# xy-pad.net
KiCad netlist of a schematic drawn in EAGLE
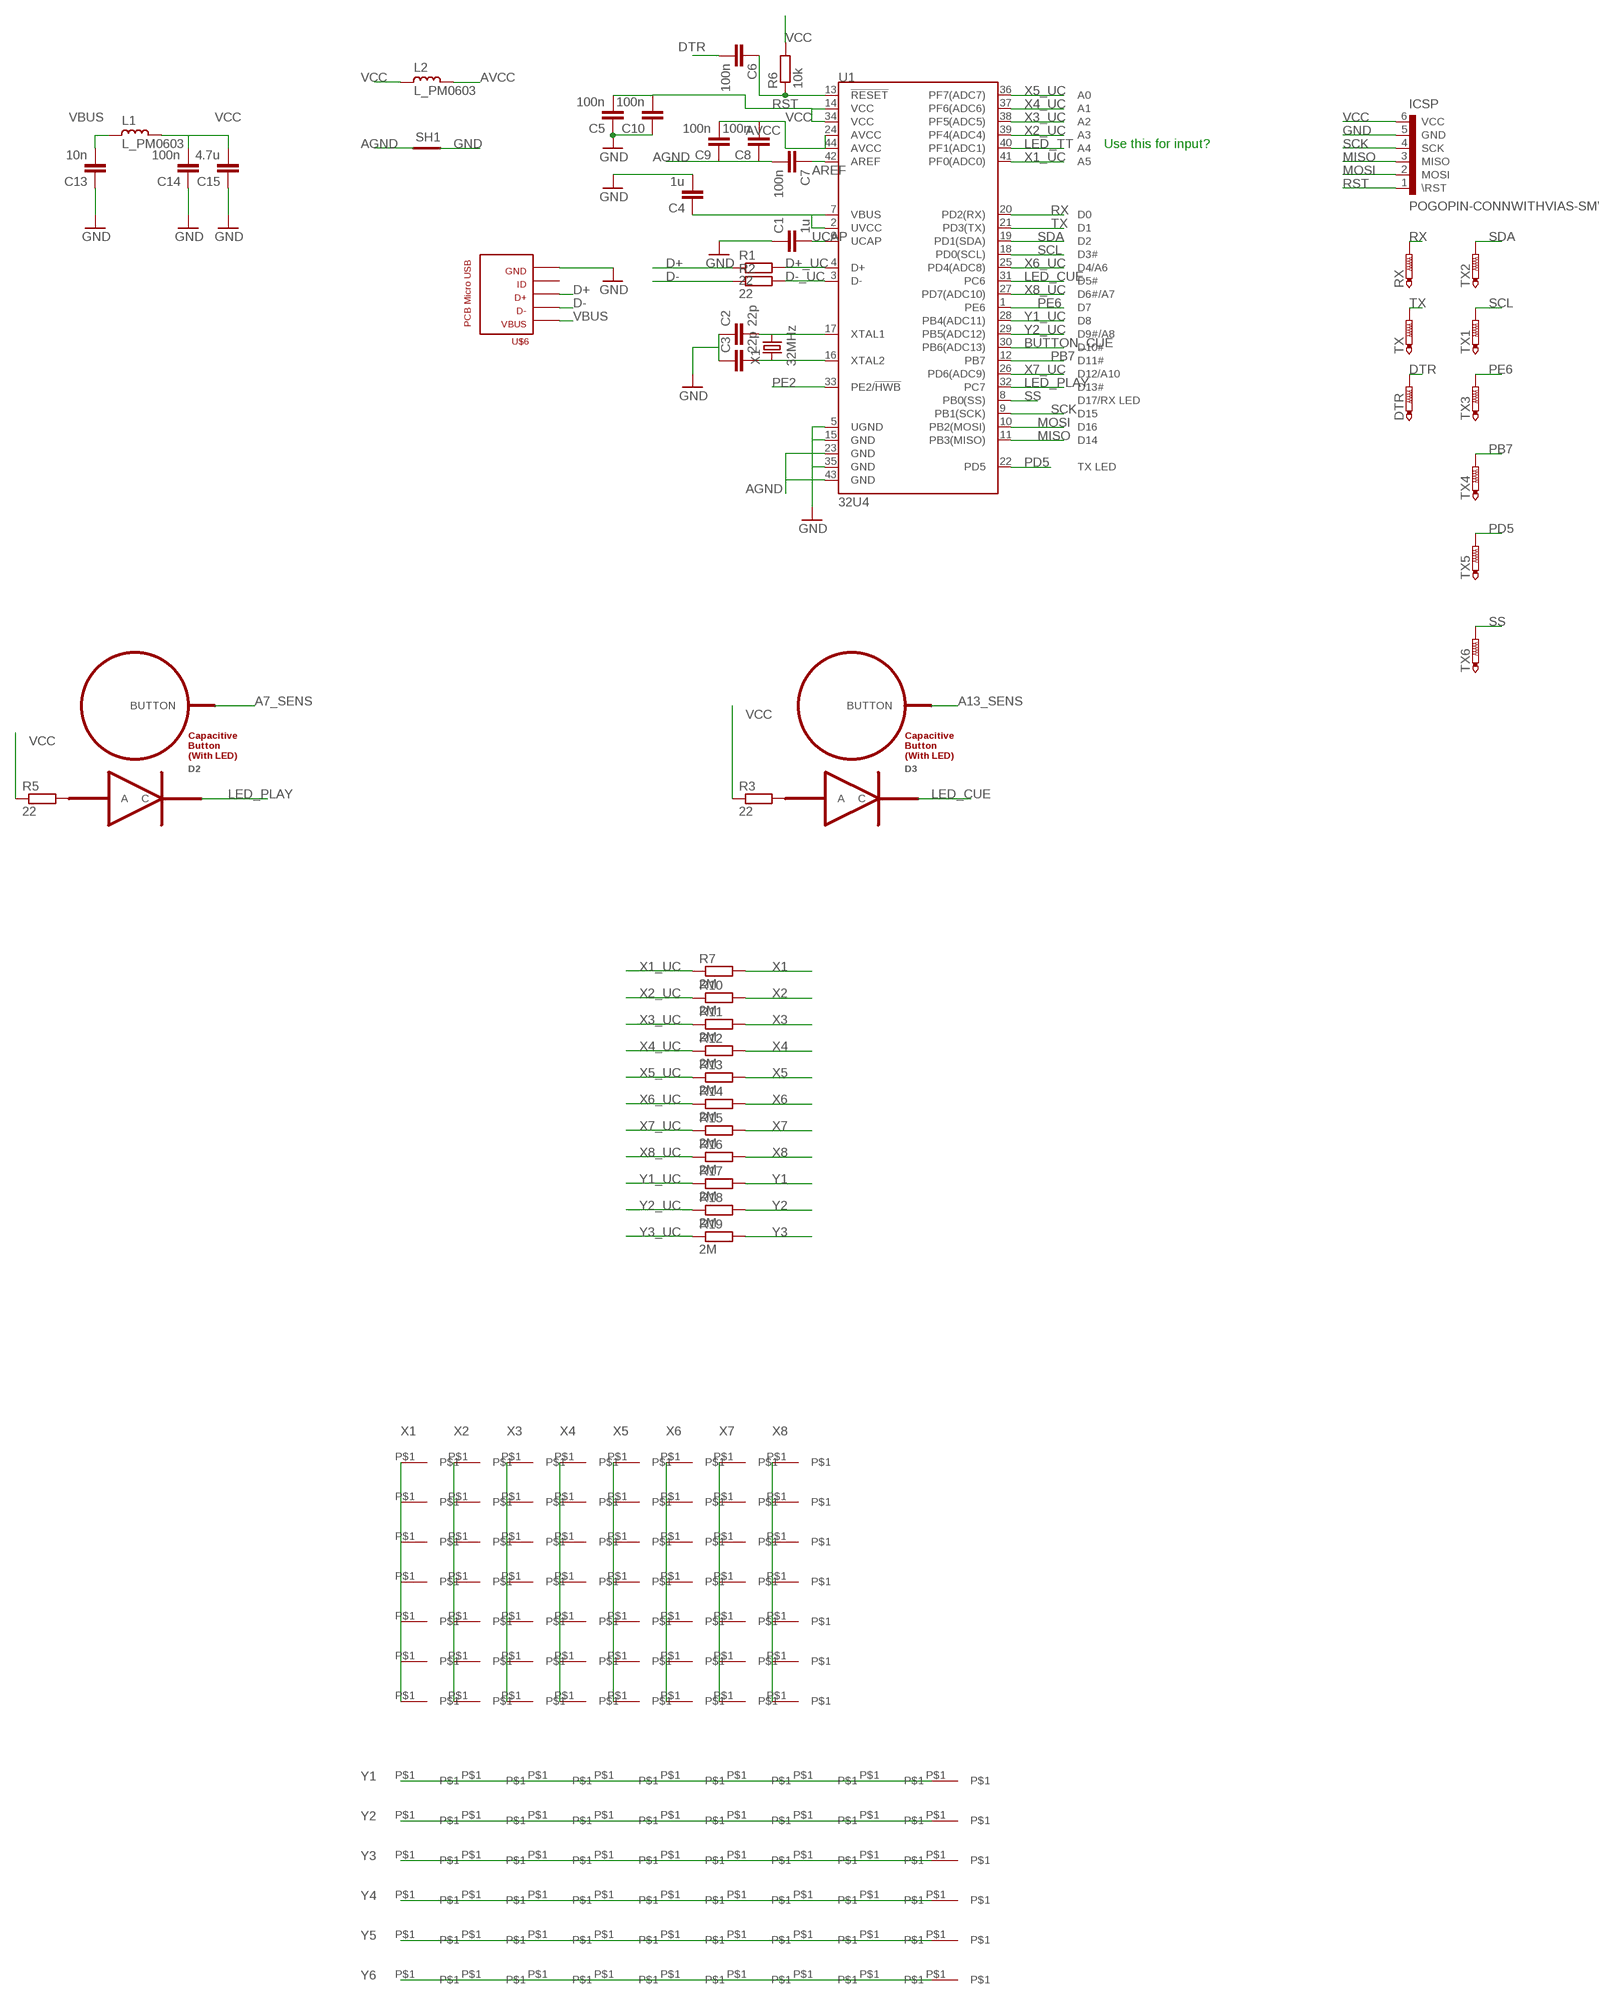
[diagram p0: schematic, sheet 1]

(export (version "E")
  (design (tool "Eeschema 10.0.6"))
  (components
    (comp (ref "C1")
      (value "1u")
      (footprint "eagle-import:C0402")
      (libsource (lib "eagle-import") (part "C-EUC0402"))
    )
    (comp (ref "C2")
      (value "22p")
      (footprint "eagle-import:C0402")
      (libsource (lib "eagle-import") (part "C-EUC0402"))
    )
    (comp (ref "C3")
      (value "22p")
      (footprint "eagle-import:C0402")
      (libsource (lib "eagle-import") (part "C-EUC0402"))
    )
    (comp (ref "C4")
      (value "1u")
      (footprint "eagle-import:C0402")
      (libsource (lib "eagle-import") (part "C-EUC0402"))
    )
    (comp (ref "C5")
      (value "100n")
      (footprint "eagle-import:C0402")
      (libsource (lib "eagle-import") (part "C-EUC0402"))
    )
    (comp (ref "C6")
      (value "100n")
      (footprint "eagle-import:C0402")
      (libsource (lib "eagle-import") (part "C-EUC0402"))
    )
    (comp (ref "C7")
      (value "100n")
      (footprint "eagle-import:C0402")
      (libsource (lib "eagle-import") (part "C-EUC0402"))
    )
    (comp (ref "C8")
      (value "100n")
      (footprint "eagle-import:C0402")
      (libsource (lib "eagle-import") (part "C-EUC0402"))
    )
    (comp (ref "C9")
      (value "100n")
      (footprint "eagle-import:C0402")
      (libsource (lib "eagle-import") (part "C-EUC0402"))
    )
    (comp (ref "C10")
      (value "100n")
      (footprint "eagle-import:C0402")
      (libsource (lib "eagle-import") (part "C-EUC0402"))
    )
    (comp (ref "C13")
      (value "10n")
      (footprint "eagle-import:C0402")
      (libsource (lib "eagle-import") (part "C-EUC0402"))
    )
    (comp (ref "C14")
      (value "100n")
      (footprint "eagle-import:C0402")
      (libsource (lib "eagle-import") (part "C-EUC0402"))
    )
    (comp (ref "C15")
      (value "4.7u")
      (footprint "eagle-import:C0402")
      (libsource (lib "eagle-import") (part "C-EUC0402"))
    )
    (comp (ref "D2")
      (value "LED_BUTTON")
      (footprint "eagle-import:LED_BUTTON")
      (libsource (lib "eagle-import") (part "LED_BUTTON"))
    )
    (comp (ref "D3")
      (value "LED_BUTTON")
      (footprint "eagle-import:LED_BUTTON")
      (libsource (lib "eagle-import") (part "LED_BUTTON"))
    )
    (comp (ref "DTR")
      (value "PTR1TP06R")
      (footprint "eagle-import:TP06R")
      (libsource (lib "eagle-import") (part "PTR1TP06R"))
    )
    (comp (ref "ICSP")
      (value "POGOPIN-CONNWITHVIAS-SMV")
      (footprint "eagle-import:POGOPROG-CONN-OH-SMALLERVIAS")
      (libsource (lib "eagle-import") (part "POGOPIN-CONNWITHVIAS-SMV"))
    )
    (comp (ref "L1")
      (value "L_PM0603")
      (footprint "eagle-import:PM0603")
      (libsource (lib "eagle-import") (part "L_PM0603"))
    )
    (comp (ref "L2")
      (value "L_PM0603")
      (footprint "eagle-import:PM0603")
      (libsource (lib "eagle-import") (part "L_PM0603"))
    )
    (comp (ref "R1")
      (value "22")
      (footprint "eagle-import:R0402")
      (libsource (lib "eagle-import") (part "R-EU_R0402"))
    )
    (comp (ref "R2")
      (value "22")
      (footprint "eagle-import:R0402")
      (libsource (lib "eagle-import") (part "R-EU_R0402"))
    )
    (comp (ref "R3")
      (value "22")
      (footprint "eagle-import:R0402")
      (libsource (lib "eagle-import") (part "R-EU_R0402"))
    )
    (comp (ref "R5")
      (value "22")
      (footprint "eagle-import:R0402")
      (libsource (lib "eagle-import") (part "R-EU_R0402"))
    )
    (comp (ref "R6")
      (value "10k")
      (footprint "eagle-import:R0402")
      (libsource (lib "eagle-import") (part "R-EU_R0402"))
    )
    (comp (ref "R7")
      (value "2M")
      (footprint "eagle-import:R0402")
      (libsource (lib "eagle-import") (part "R-EU_R0402"))
    )
    (comp (ref "R10")
      (value "2M")
      (footprint "eagle-import:R0402")
      (libsource (lib "eagle-import") (part "R-EU_R0402"))
    )
    (comp (ref "R11")
      (value "2M")
      (footprint "eagle-import:R0402")
      (libsource (lib "eagle-import") (part "R-EU_R0402"))
    )
    (comp (ref "R12")
      (value "2M")
      (footprint "eagle-import:R0402")
      (libsource (lib "eagle-import") (part "R-EU_R0402"))
    )
    (comp (ref "R13")
      (value "2M")
      (footprint "eagle-import:R0402")
      (libsource (lib "eagle-import") (part "R-EU_R0402"))
    )
    (comp (ref "R14")
      (value "2M")
      (footprint "eagle-import:R0402")
      (libsource (lib "eagle-import") (part "R-EU_R0402"))
    )
    (comp (ref "R15")
      (value "2M")
      (footprint "eagle-import:R0402")
      (libsource (lib "eagle-import") (part "R-EU_R0402"))
    )
    (comp (ref "R16")
      (value "2M")
      (footprint "eagle-import:R0402")
      (libsource (lib "eagle-import") (part "R-EU_R0402"))
    )
    (comp (ref "R17")
      (value "2M")
      (footprint "eagle-import:R0402")
      (libsource (lib "eagle-import") (part "R-EU_R0402"))
    )
    (comp (ref "R18")
      (value "2M")
      (footprint "eagle-import:R0402")
      (libsource (lib "eagle-import") (part "R-EU_R0402"))
    )
    (comp (ref "R19")
      (value "2M")
      (footprint "eagle-import:R0402")
      (libsource (lib "eagle-import") (part "R-EU_R0402"))
    )
    (comp (ref "RX")
      (value "PTR1TP06R")
      (footprint "eagle-import:TP06R")
      (libsource (lib "eagle-import") (part "PTR1TP06R"))
    )
    (comp (ref "SH1")
      (value "SHORT")
      (footprint "eagle-import:SHORT_TOP-6")
      (libsource (lib "eagle-import") (part "SHORT"))
    )
    (comp (ref "TX")
      (value "PTR1TP06R")
      (footprint "eagle-import:TP06R")
      (libsource (lib "eagle-import") (part "PTR1TP06R"))
    )
    (comp (ref "TX1")
      (value "PTR1TP06R")
      (footprint "eagle-import:TP06R")
      (libsource (lib "eagle-import") (part "PTR1TP06R"))
    )
    (comp (ref "TX2")
      (value "PTR1TP06R")
      (footprint "eagle-import:TP06R")
      (libsource (lib "eagle-import") (part "PTR1TP06R"))
    )
    (comp (ref "TX3")
      (value "PTR1TP06R")
      (footprint "eagle-import:TP06R")
      (libsource (lib "eagle-import") (part "PTR1TP06R"))
    )
    (comp (ref "TX4")
      (value "PTR1TP06R")
      (footprint "eagle-import:TP06R")
      (libsource (lib "eagle-import") (part "PTR1TP06R"))
    )
    (comp (ref "TX5")
      (value "PTR1TP06R")
      (footprint "eagle-import:TP06R")
      (libsource (lib "eagle-import") (part "PTR1TP06R"))
    )
    (comp (ref "TX6")
      (value "PTR1TP06R")
      (footprint "eagle-import:TP06R")
      (libsource (lib "eagle-import") (part "PTR1TP06R"))
    )
    (comp (ref "U$1")
      (value "XY_PAD")
      (footprint "eagle-import:DIAMOND_PAD")
      (libsource (lib "eagle-import") (part "XY_PAD"))
    )
    (comp (ref "U$2")
      (value "XY_PADTRIANGLE")
      (footprint "eagle-import:TRIANGLE_PAD")
      (libsource (lib "eagle-import") (part "XY_PADTRIANGLE"))
    )
    (comp (ref "U$3")
      (value "XY_PADTRIANGLE")
      (footprint "eagle-import:TRIANGLE_PAD")
      (libsource (lib "eagle-import") (part "XY_PADTRIANGLE"))
    )
    (comp (ref "U$4")
      (value "XY_PADTRIANGLE")
      (footprint "eagle-import:TRIANGLE_PAD")
      (libsource (lib "eagle-import") (part "XY_PADTRIANGLE"))
    )
    (comp (ref "U$5")
      (value "XY_PADTRIANGLE")
      (footprint "eagle-import:TRIANGLE_PAD")
      (libsource (lib "eagle-import") (part "XY_PADTRIANGLE"))
    )
    (comp (ref "U$6")
      (value "PCB_MICRO_USB_BSS_2")
      (footprint "eagle-import:USB_TYPE_B_SS_2")
      (libsource (lib "eagle-import") (part "PCB_MICRO_USB_BSS_2"))
    )
    (comp (ref "U$7")
      (value "XY_PADTRIANGLE")
      (footprint "eagle-import:TRIANGLE_PAD")
      (libsource (lib "eagle-import") (part "XY_PADTRIANGLE"))
    )
    (comp (ref "U$8")
      (value "XY_PADTRIANGLE")
      (footprint "eagle-import:TRIANGLE_PAD")
      (libsource (lib "eagle-import") (part "XY_PADTRIANGLE"))
    )
    (comp (ref "U$9")
      (value "XY_PADTRIANGLE")
      (footprint "eagle-import:TRIANGLE_PAD")
      (libsource (lib "eagle-import") (part "XY_PADTRIANGLE"))
    )
    (comp (ref "U$10")
      (value "XY_PADTRIANGLE")
      (footprint "eagle-import:TRIANGLE_PAD")
      (libsource (lib "eagle-import") (part "XY_PADTRIANGLE"))
    )
    (comp (ref "U$11")
      (value "XY_PAD")
      (footprint "eagle-import:DIAMOND_PAD")
      (libsource (lib "eagle-import") (part "XY_PAD"))
    )
    (comp (ref "U$12")
      (value "XY_PAD")
      (footprint "eagle-import:DIAMOND_PAD")
      (libsource (lib "eagle-import") (part "XY_PAD"))
    )
    (comp (ref "U$13")
      (value "XY_PAD")
      (footprint "eagle-import:DIAMOND_PAD")
      (libsource (lib "eagle-import") (part "XY_PAD"))
    )
    (comp (ref "U$14")
      (value "XY_PAD")
      (footprint "eagle-import:DIAMOND_PAD")
      (libsource (lib "eagle-import") (part "XY_PAD"))
    )
    (comp (ref "U$15")
      (value "XY_PAD")
      (footprint "eagle-import:DIAMOND_PAD")
      (libsource (lib "eagle-import") (part "XY_PAD"))
    )
    (comp (ref "U$16")
      (value "XY_PAD")
      (footprint "eagle-import:DIAMOND_PAD")
      (libsource (lib "eagle-import") (part "XY_PAD"))
    )
    (comp (ref "U$17")
      (value "XY_PAD")
      (footprint "eagle-import:DIAMOND_PAD")
      (libsource (lib "eagle-import") (part "XY_PAD"))
    )
    (comp (ref "U$18")
      (value "XY_PAD")
      (footprint "eagle-import:DIAMOND_PAD")
      (libsource (lib "eagle-import") (part "XY_PAD"))
    )
    (comp (ref "U$19")
      (value "XY_PAD")
      (footprint "eagle-import:DIAMOND_PAD")
      (libsource (lib "eagle-import") (part "XY_PAD"))
    )
    (comp (ref "U$20")
      (value "XY_PAD")
      (footprint "eagle-import:DIAMOND_PAD")
      (libsource (lib "eagle-import") (part "XY_PAD"))
    )
    (comp (ref "U$21")
      (value "XY_PAD")
      (footprint "eagle-import:DIAMOND_PAD")
      (libsource (lib "eagle-import") (part "XY_PAD"))
    )
    (comp (ref "U$22")
      (value "XY_PAD")
      (footprint "eagle-import:DIAMOND_PAD")
      (libsource (lib "eagle-import") (part "XY_PAD"))
    )
    (comp (ref "U$23")
      (value "XY_PAD")
      (footprint "eagle-import:DIAMOND_PAD")
      (libsource (lib "eagle-import") (part "XY_PAD"))
    )
    (comp (ref "U$24")
      (value "XY_PAD")
      (footprint "eagle-import:DIAMOND_PAD")
      (libsource (lib "eagle-import") (part "XY_PAD"))
    )
    (comp (ref "U$25")
      (value "XY_PAD")
      (footprint "eagle-import:DIAMOND_PAD")
      (libsource (lib "eagle-import") (part "XY_PAD"))
    )
    (comp (ref "U$26")
      (value "XY_PAD")
      (footprint "eagle-import:DIAMOND_PAD")
      (libsource (lib "eagle-import") (part "XY_PAD"))
    )
    (comp (ref "U$27")
      (value "XY_PAD")
      (footprint "eagle-import:DIAMOND_PAD")
      (libsource (lib "eagle-import") (part "XY_PAD"))
    )
    (comp (ref "U$28")
      (value "XY_PAD")
      (footprint "eagle-import:DIAMOND_PAD")
      (libsource (lib "eagle-import") (part "XY_PAD"))
    )
    (comp (ref "U$29")
      (value "XY_PAD")
      (footprint "eagle-import:DIAMOND_PAD")
      (libsource (lib "eagle-import") (part "XY_PAD"))
    )
    (comp (ref "U$30")
      (value "XY_PAD")
      (footprint "eagle-import:DIAMOND_PAD")
      (libsource (lib "eagle-import") (part "XY_PAD"))
    )
    (comp (ref "U$31")
      (value "XY_PAD")
      (footprint "eagle-import:DIAMOND_PAD")
      (libsource (lib "eagle-import") (part "XY_PAD"))
    )
    (comp (ref "U$32")
      (value "XY_PAD")
      (footprint "eagle-import:DIAMOND_PAD")
      (libsource (lib "eagle-import") (part "XY_PAD"))
    )
    (comp (ref "U$33")
      (value "XY_PAD")
      (footprint "eagle-import:DIAMOND_PAD")
      (libsource (lib "eagle-import") (part "XY_PAD"))
    )
    (comp (ref "U$34")
      (value "XY_PAD")
      (footprint "eagle-import:DIAMOND_PAD")
      (libsource (lib "eagle-import") (part "XY_PAD"))
    )
    (comp (ref "U$35")
      (value "XY_PAD")
      (footprint "eagle-import:DIAMOND_PAD")
      (libsource (lib "eagle-import") (part "XY_PAD"))
    )
    (comp (ref "U$36")
      (value "XY_PAD")
      (footprint "eagle-import:DIAMOND_PAD")
      (libsource (lib "eagle-import") (part "XY_PAD"))
    )
    (comp (ref "U$37")
      (value "XY_PAD")
      (footprint "eagle-import:DIAMOND_PAD")
      (libsource (lib "eagle-import") (part "XY_PAD"))
    )
    (comp (ref "U$38")
      (value "XY_PAD")
      (footprint "eagle-import:DIAMOND_PAD")
      (libsource (lib "eagle-import") (part "XY_PAD"))
    )
    (comp (ref "U$39")
      (value "XY_PAD")
      (footprint "eagle-import:DIAMOND_PAD")
      (libsource (lib "eagle-import") (part "XY_PAD"))
    )
    (comp (ref "U$40")
      (value "XY_PAD")
      (footprint "eagle-import:DIAMOND_PAD")
      (libsource (lib "eagle-import") (part "XY_PAD"))
    )
    (comp (ref "U$41")
      (value "XY_PAD")
      (footprint "eagle-import:DIAMOND_PAD")
      (libsource (lib "eagle-import") (part "XY_PAD"))
    )
    (comp (ref "U$42")
      (value "XY_PAD")
      (footprint "eagle-import:DIAMOND_PAD")
      (libsource (lib "eagle-import") (part "XY_PAD"))
    )
    (comp (ref "U$43")
      (value "XY_PAD")
      (footprint "eagle-import:DIAMOND_PAD")
      (libsource (lib "eagle-import") (part "XY_PAD"))
    )
    (comp (ref "U$44")
      (value "XY_PAD")
      (footprint "eagle-import:DIAMOND_PAD")
      (libsource (lib "eagle-import") (part "XY_PAD"))
    )
    (comp (ref "U$45")
      (value "XY_PAD")
      (footprint "eagle-import:DIAMOND_PAD")
      (libsource (lib "eagle-import") (part "XY_PAD"))
    )
    (comp (ref "U$46")
      (value "XY_PAD")
      (footprint "eagle-import:DIAMOND_PAD")
      (libsource (lib "eagle-import") (part "XY_PAD"))
    )
    (comp (ref "U$47")
      (value "XY_PAD")
      (footprint "eagle-import:DIAMOND_PAD")
      (libsource (lib "eagle-import") (part "XY_PAD"))
    )
    (comp (ref "U$48")
      (value "XY_PAD")
      (footprint "eagle-import:DIAMOND_PAD")
      (libsource (lib "eagle-import") (part "XY_PAD"))
    )
    (comp (ref "U$49")
      (value "XY_PAD")
      (footprint "eagle-import:DIAMOND_PAD")
      (libsource (lib "eagle-import") (part "XY_PAD"))
    )
    (comp (ref "U$50")
      (value "XY_PADTRIANGLE")
      (footprint "eagle-import:TRIANGLE_PAD")
      (libsource (lib "eagle-import") (part "XY_PADTRIANGLE"))
    )
    (comp (ref "U$51")
      (value "XY_PADTRIANGLE")
      (footprint "eagle-import:TRIANGLE_PAD")
      (libsource (lib "eagle-import") (part "XY_PADTRIANGLE"))
    )
    (comp (ref "U$52")
      (value "XY_PADTRIANGLE")
      (footprint "eagle-import:TRIANGLE_PAD")
      (libsource (lib "eagle-import") (part "XY_PADTRIANGLE"))
    )
    (comp (ref "U$53")
      (value "XY_PADTRIANGLE")
      (footprint "eagle-import:TRIANGLE_PAD")
      (libsource (lib "eagle-import") (part "XY_PADTRIANGLE"))
    )
    (comp (ref "U$54")
      (value "XY_PADTRIANGLE")
      (footprint "eagle-import:TRIANGLE_PAD")
      (libsource (lib "eagle-import") (part "XY_PADTRIANGLE"))
    )
    (comp (ref "U$55")
      (value "XY_PADTRIANGLE")
      (footprint "eagle-import:TRIANGLE_PAD")
      (libsource (lib "eagle-import") (part "XY_PADTRIANGLE"))
    )
    (comp (ref "U$56")
      (value "XY_PADTRIANGLE")
      (footprint "eagle-import:TRIANGLE_PAD")
      (libsource (lib "eagle-import") (part "XY_PADTRIANGLE"))
    )
    (comp (ref "U$57")
      (value "XY_PADTRIANGLE")
      (footprint "eagle-import:TRIANGLE_PAD")
      (libsource (lib "eagle-import") (part "XY_PADTRIANGLE"))
    )
    (comp (ref "U$58")
      (value "XY_PADTRIANGLE")
      (footprint "eagle-import:TRIANGLE_PAD")
      (libsource (lib "eagle-import") (part "XY_PADTRIANGLE"))
    )
    (comp (ref "U$59")
      (value "XY_PADTRIANGLE")
      (footprint "eagle-import:TRIANGLE_PAD")
      (libsource (lib "eagle-import") (part "XY_PADTRIANGLE"))
    )
    (comp (ref "U$60")
      (value "XY_PADTRIANGLE")
      (footprint "eagle-import:TRIANGLE_PAD")
      (libsource (lib "eagle-import") (part "XY_PADTRIANGLE"))
    )
    (comp (ref "U$61")
      (value "XY_PADTRIANGLE")
      (footprint "eagle-import:TRIANGLE_PAD")
      (libsource (lib "eagle-import") (part "XY_PADTRIANGLE"))
    )
    (comp (ref "U$62")
      (value "XY_PADTRIANGLE")
      (footprint "eagle-import:TRIANGLE_PAD")
      (libsource (lib "eagle-import") (part "XY_PADTRIANGLE"))
    )
    (comp (ref "U$63")
      (value "XY_PADTRIANGLE")
      (footprint "eagle-import:TRIANGLE_PAD")
      (libsource (lib "eagle-import") (part "XY_PADTRIANGLE"))
    )
    (comp (ref "U$64")
      (value "XY_PAD")
      (footprint "eagle-import:DIAMOND_PAD")
      (libsource (lib "eagle-import") (part "XY_PAD"))
    )
    (comp (ref "U$65")
      (value "XY_PAD")
      (footprint "eagle-import:DIAMOND_PAD")
      (libsource (lib "eagle-import") (part "XY_PAD"))
    )
    (comp (ref "U$66")
      (value "XY_PAD")
      (footprint "eagle-import:DIAMOND_PAD")
      (libsource (lib "eagle-import") (part "XY_PAD"))
    )
    (comp (ref "U$67")
      (value "XY_PAD")
      (footprint "eagle-import:DIAMOND_PAD")
      (libsource (lib "eagle-import") (part "XY_PAD"))
    )
    (comp (ref "U$68")
      (value "XY_PAD")
      (footprint "eagle-import:DIAMOND_PAD")
      (libsource (lib "eagle-import") (part "XY_PAD"))
    )
    (comp (ref "U$69")
      (value "XY_PAD")
      (footprint "eagle-import:DIAMOND_PAD")
      (libsource (lib "eagle-import") (part "XY_PAD"))
    )
    (comp (ref "U$70")
      (value "XY_PAD")
      (footprint "eagle-import:DIAMOND_PAD")
      (libsource (lib "eagle-import") (part "XY_PAD"))
    )
    (comp (ref "U$71")
      (value "XY_PAD")
      (footprint "eagle-import:DIAMOND_PAD")
      (libsource (lib "eagle-import") (part "XY_PAD"))
    )
    (comp (ref "U$72")
      (value "XY_PAD")
      (footprint "eagle-import:DIAMOND_PAD")
      (libsource (lib "eagle-import") (part "XY_PAD"))
    )
    (comp (ref "U$73")
      (value "XY_PAD")
      (footprint "eagle-import:DIAMOND_PAD")
      (libsource (lib "eagle-import") (part "XY_PAD"))
    )
    (comp (ref "U$74")
      (value "XY_PAD")
      (footprint "eagle-import:DIAMOND_PAD")
      (libsource (lib "eagle-import") (part "XY_PAD"))
    )
    (comp (ref "U$75")
      (value "XY_PAD")
      (footprint "eagle-import:DIAMOND_PAD")
      (libsource (lib "eagle-import") (part "XY_PAD"))
    )
    (comp (ref "U$76")
      (value "XY_PAD")
      (footprint "eagle-import:DIAMOND_PAD")
      (libsource (lib "eagle-import") (part "XY_PAD"))
    )
    (comp (ref "U$77")
      (value "XY_PAD")
      (footprint "eagle-import:DIAMOND_PAD")
      (libsource (lib "eagle-import") (part "XY_PAD"))
    )
    (comp (ref "U$78")
      (value "XY_PAD")
      (footprint "eagle-import:DIAMOND_PAD")
      (libsource (lib "eagle-import") (part "XY_PAD"))
    )
    (comp (ref "U$79")
      (value "XY_PAD")
      (footprint "eagle-import:DIAMOND_PAD")
      (libsource (lib "eagle-import") (part "XY_PAD"))
    )
    (comp (ref "U$80")
      (value "XY_PAD")
      (footprint "eagle-import:DIAMOND_PAD")
      (libsource (lib "eagle-import") (part "XY_PAD"))
    )
    (comp (ref "U$81")
      (value "XY_PAD")
      (footprint "eagle-import:DIAMOND_PAD")
      (libsource (lib "eagle-import") (part "XY_PAD"))
    )
    (comp (ref "U$82")
      (value "XY_PAD")
      (footprint "eagle-import:DIAMOND_PAD")
      (libsource (lib "eagle-import") (part "XY_PAD"))
    )
    (comp (ref "U$83")
      (value "XY_PAD")
      (footprint "eagle-import:DIAMOND_PAD")
      (libsource (lib "eagle-import") (part "XY_PAD"))
    )
    (comp (ref "U$84")
      (value "XY_PAD")
      (footprint "eagle-import:DIAMOND_PAD")
      (libsource (lib "eagle-import") (part "XY_PAD"))
    )
    (comp (ref "U$85")
      (value "XY_PAD")
      (footprint "eagle-import:DIAMOND_PAD")
      (libsource (lib "eagle-import") (part "XY_PAD"))
    )
    (comp (ref "U$86")
      (value "XY_PAD")
      (footprint "eagle-import:DIAMOND_PAD")
      (libsource (lib "eagle-import") (part "XY_PAD"))
    )
    (comp (ref "U$87")
      (value "XY_PAD")
      (footprint "eagle-import:DIAMOND_PAD")
      (libsource (lib "eagle-import") (part "XY_PAD"))
    )
    (comp (ref "U$88")
      (value "XY_PAD")
      (footprint "eagle-import:DIAMOND_PAD")
      (libsource (lib "eagle-import") (part "XY_PAD"))
    )
    (comp (ref "U$89")
      (value "XY_PAD")
      (footprint "eagle-import:DIAMOND_PAD")
      (libsource (lib "eagle-import") (part "XY_PAD"))
    )
    (comp (ref "U$90")
      (value "XY_PAD")
      (footprint "eagle-import:DIAMOND_PAD")
      (libsource (lib "eagle-import") (part "XY_PAD"))
    )
    (comp (ref "U$91")
      (value "XY_PAD")
      (footprint "eagle-import:DIAMOND_PAD")
      (libsource (lib "eagle-import") (part "XY_PAD"))
    )
    (comp (ref "U$92")
      (value "XY_PAD")
      (footprint "eagle-import:DIAMOND_PAD")
      (libsource (lib "eagle-import") (part "XY_PAD"))
    )
    (comp (ref "U$93")
      (value "XY_PAD")
      (footprint "eagle-import:DIAMOND_PAD")
      (libsource (lib "eagle-import") (part "XY_PAD"))
    )
    (comp (ref "U$94")
      (value "XY_PAD")
      (footprint "eagle-import:DIAMOND_PAD")
      (libsource (lib "eagle-import") (part "XY_PAD"))
    )
    (comp (ref "U$95")
      (value "XY_PAD")
      (footprint "eagle-import:DIAMOND_PAD")
      (libsource (lib "eagle-import") (part "XY_PAD"))
    )
    (comp (ref "U$96")
      (value "XY_PAD")
      (footprint "eagle-import:DIAMOND_PAD")
      (libsource (lib "eagle-import") (part "XY_PAD"))
    )
    (comp (ref "U$97")
      (value "XY_PAD")
      (footprint "eagle-import:DIAMOND_PAD")
      (libsource (lib "eagle-import") (part "XY_PAD"))
    )
    (comp (ref "U$98")
      (value "XY_PAD")
      (footprint "eagle-import:DIAMOND_PAD")
      (libsource (lib "eagle-import") (part "XY_PAD"))
    )
    (comp (ref "U$99")
      (value "XY_PAD")
      (footprint "eagle-import:DIAMOND_PAD")
      (libsource (lib "eagle-import") (part "XY_PAD"))
    )
    (comp (ref "U$100")
      (value "XY_PAD")
      (footprint "eagle-import:DIAMOND_PAD")
      (libsource (lib "eagle-import") (part "XY_PAD"))
    )
    (comp (ref "U$101")
      (value "XY_PAD")
      (footprint "eagle-import:DIAMOND_PAD")
      (libsource (lib "eagle-import") (part "XY_PAD"))
    )
    (comp (ref "U$102")
      (value "XY_PAD")
      (footprint "eagle-import:DIAMOND_PAD")
      (libsource (lib "eagle-import") (part "XY_PAD"))
    )
    (comp (ref "U$103")
      (value "XY_PAD")
      (footprint "eagle-import:DIAMOND_PAD")
      (libsource (lib "eagle-import") (part "XY_PAD"))
    )
    (comp (ref "U$104")
      (value "XY_PAD")
      (footprint "eagle-import:DIAMOND_PAD")
      (libsource (lib "eagle-import") (part "XY_PAD"))
    )
    (comp (ref "U$105")
      (value "XY_PAD")
      (footprint "eagle-import:DIAMOND_PAD")
      (libsource (lib "eagle-import") (part "XY_PAD"))
    )
    (comp (ref "U$106")
      (value "XY_PADTRIANGLE")
      (footprint "eagle-import:TRIANGLE_PAD")
      (libsource (lib "eagle-import") (part "XY_PADTRIANGLE"))
    )
    (comp (ref "U$107")
      (value "XY_PADTRIANGLE")
      (footprint "eagle-import:TRIANGLE_PAD")
      (libsource (lib "eagle-import") (part "XY_PADTRIANGLE"))
    )
    (comp (ref "U$108")
      (value "XY_PADTRIANGLE")
      (footprint "eagle-import:TRIANGLE_PAD")
      (libsource (lib "eagle-import") (part "XY_PADTRIANGLE"))
    )
    (comp (ref "U$109")
      (value "XY_PADTRIANGLE")
      (footprint "eagle-import:TRIANGLE_PAD")
      (libsource (lib "eagle-import") (part "XY_PADTRIANGLE"))
    )
    (comp (ref "U$110")
      (value "XY_PADTRIANGLE")
      (footprint "eagle-import:TRIANGLE_PAD")
      (libsource (lib "eagle-import") (part "XY_PADTRIANGLE"))
    )
    (comp (ref "U$111")
      (value "XY_PADTRIANGLE")
      (footprint "eagle-import:TRIANGLE_PAD")
      (libsource (lib "eagle-import") (part "XY_PADTRIANGLE"))
    )
    (comp (ref "U1")
      (value "32U4")
      (footprint "eagle-import:QFN-44")
      (libsource (lib "eagle-import") (part "ATMEGA32U4QFN"))
    )
    (comp (ref "X1")
      (value "32MHz")
      (footprint "eagle-import:CRYSTAL-SMD-2.0X1.6MM")
      (libsource (lib "eagle-import") (part "CRYSTAL-32MHZ-SMD-2.0X1.6MM"))
    )
  )
  (nets
    (net (code "1") (name "/A7_SENS") (class "Default")
      (node (ref "D2") (pin "BUTTON") (pinfunction "BUTTON_BUTTON") (pintype "passive"))
    )
    (net (code "2") (name "/A13_SENS") (class "Default")
      (node (ref "D3") (pin "BUTTON") (pinfunction "BUTTON_BUTTON") (pintype "passive"))
    )
    (net (code "3") (name "/AGND") (class "Default")
      (node (ref "C7") (pin "2") (pinfunction "2_2") (pintype "passive"))
      (node (ref "C8") (pin "1") (pinfunction "1_1") (pintype "passive"))
      (node (ref "C9") (pin "1") (pinfunction "1_1") (pintype "passive"))
      (node (ref "SH1") (pin "1") (pinfunction "P$1_1") (pintype "bidirectional"))
      (node (ref "U1") (pin "23") (pinfunction "GND_23") (pintype "bidirectional"))
      (node (ref "U1") (pin "43") (pinfunction "GND_43") (pintype "bidirectional"))
    )
    (net (code "4") (name "/AREF") (class "Default")
      (node (ref "C7") (pin "1") (pinfunction "1_1") (pintype "passive"))
      (node (ref "U1") (pin "42") (pinfunction "AREF_42") (pintype "bidirectional"))
    )
    (net (code "5") (name "/AVCC") (class "Default")
      (node (ref "C8") (pin "2") (pinfunction "2_2") (pintype "passive"))
      (node (ref "C9") (pin "2") (pinfunction "2_2") (pintype "passive"))
      (node (ref "L2") (pin "1") (pinfunction "1_1") (pintype "passive"))
      (node (ref "U1") (pin "24") (pinfunction "AVCC_24") (pintype "bidirectional"))
      (node (ref "U1") (pin "44") (pinfunction "AVCC_44") (pintype "bidirectional"))
    )
    (net (code "6") (name "/BUTTON_CUE") (class "Default")
      (node (ref "U1") (pin "30") (pinfunction "PB6(ADC13)_30") (pintype "bidirectional"))
    )
    (net (code "7") (name "/D+") (class "Default")
      (node (ref "R1") (pin "1") (pinfunction "1_1") (pintype "passive"))
      (node (ref "U$6") (pin "3") (pinfunction "3_3") (pintype "bidirectional"))
    )
    (net (code "8") (name "/D+_UC") (class "Default")
      (node (ref "R1") (pin "2") (pinfunction "2_2") (pintype "passive"))
      (node (ref "U1") (pin "4") (pinfunction "D+_4") (pintype "bidirectional"))
    )
    (net (code "9") (name "/D-") (class "Default")
      (node (ref "R2") (pin "1") (pinfunction "1_1") (pintype "passive"))
      (node (ref "U$6") (pin "2") (pinfunction "2_2") (pintype "bidirectional"))
    )
    (net (code "10") (name "/D-_UC") (class "Default")
      (node (ref "R2") (pin "2") (pinfunction "2_2") (pintype "passive"))
      (node (ref "U1") (pin "3") (pinfunction "D-_3") (pintype "bidirectional"))
    )
    (net (code "11") (name "/DTR") (class "Default")
      (node (ref "C6") (pin "2") (pinfunction "2_2") (pintype "passive"))
      (node (ref "DTR") (pin "TP") (pinfunction "TP_TP") (pintype "input"))
    )
    (net (code "12") (name "/LED_CUE") (class "Default")
      (node (ref "D3") (pin "C") (pinfunction "C_C") (pintype "bidirectional"))
      (node (ref "U1") (pin "31") (pinfunction "PC6_31") (pintype "bidirectional"))
    )
    (net (code "13") (name "/LED_PLAY") (class "Default")
      (node (ref "D2") (pin "C") (pinfunction "C_C") (pintype "bidirectional"))
      (node (ref "U1") (pin "32") (pinfunction "PC7_32") (pintype "bidirectional"))
    )
    (net (code "14") (name "/LED_TT") (class "Default")
      (node (ref "U1") (pin "40") (pinfunction "PF1(ADC1)_40") (pintype "bidirectional"))
    )
    (net (code "15") (name "/MISO") (class "Default")
      (node (ref "ICSP") (pin "3") (pinfunction "MISO_3") (pintype "bidirectional"))
      (node (ref "U1") (pin "11") (pinfunction "PB3(MISO)_11") (pintype "bidirectional"))
    )
    (net (code "16") (name "/MOSI") (class "Default")
      (node (ref "ICSP") (pin "2") (pinfunction "MOSI_2") (pintype "bidirectional"))
      (node (ref "U1") (pin "10") (pinfunction "PB2(MOSI)_10") (pintype "bidirectional"))
    )
    (net (code "17") (name "/PB7") (class "Default")
      (node (ref "TX4") (pin "TP") (pinfunction "TP_TP") (pintype "input"))
      (node (ref "U1") (pin "12") (pinfunction "PB7_12") (pintype "bidirectional"))
    )
    (net (code "18") (name "/PD5") (class "Default")
      (node (ref "TX5") (pin "TP") (pinfunction "TP_TP") (pintype "input"))
      (node (ref "U1") (pin "22") (pinfunction "PD5_22") (pintype "bidirectional"))
    )
    (net (code "19") (name "/PE2") (class "Default")
      (node (ref "U1") (pin "33") (pinfunction "PE2/~{HWB}_33") (pintype "bidirectional"))
    )
    (net (code "20") (name "/PE6") (class "Default")
      (node (ref "TX3") (pin "TP") (pinfunction "TP_TP") (pintype "input"))
      (node (ref "U1") (pin "1") (pinfunction "PE6_1") (pintype "bidirectional"))
    )
    (net (code "21") (name "/RST") (class "Default")
      (node (ref "C6") (pin "1") (pinfunction "1_1") (pintype "passive"))
      (node (ref "ICSP") (pin "1") (pinfunction "\\RST_1") (pintype "bidirectional"))
      (node (ref "R6") (pin "1") (pinfunction "1_1") (pintype "passive"))
      (node (ref "U1") (pin "13") (pinfunction "~{RESET}_13") (pintype "bidirectional"))
    )
    (net (code "22") (name "/RX") (class "Default")
      (node (ref "RX") (pin "TP") (pinfunction "TP_TP") (pintype "input"))
      (node (ref "U1") (pin "20") (pinfunction "PD2(RX)_20") (pintype "bidirectional"))
    )
    (net (code "23") (name "/SCK") (class "Default")
      (node (ref "ICSP") (pin "4") (pinfunction "SCK_4") (pintype "bidirectional"))
      (node (ref "U1") (pin "9") (pinfunction "PB1(SCK)_9") (pintype "bidirectional"))
    )
    (net (code "24") (name "/SCL") (class "Default")
      (node (ref "TX1") (pin "TP") (pinfunction "TP_TP") (pintype "input"))
      (node (ref "U1") (pin "18") (pinfunction "PD0(SCL)_18") (pintype "bidirectional"))
    )
    (net (code "25") (name "/SDA") (class "Default")
      (node (ref "TX2") (pin "TP") (pinfunction "TP_TP") (pintype "input"))
      (node (ref "U1") (pin "19") (pinfunction "PD1(SDA)_19") (pintype "bidirectional"))
    )
    (net (code "26") (name "/SS") (class "Default")
      (node (ref "TX6") (pin "TP") (pinfunction "TP_TP") (pintype "input"))
      (node (ref "U1") (pin "8") (pinfunction "PB0(SS)_8") (pintype "bidirectional"))
    )
    (net (code "27") (name "/TX") (class "Default")
      (node (ref "TX") (pin "TP") (pinfunction "TP_TP") (pintype "input"))
      (node (ref "U1") (pin "21") (pinfunction "PD3(TX)_21") (pintype "bidirectional"))
    )
    (net (code "28") (name "/UCAP") (class "Default")
      (node (ref "C1") (pin "2") (pinfunction "2_2") (pintype "passive"))
      (node (ref "U1") (pin "6") (pinfunction "UCAP_6") (pintype "bidirectional"))
    )
    (net (code "29") (name "/VBUS") (class "Default")
      (node (ref "C13") (pin "2") (pinfunction "2_2") (pintype "passive"))
      (node (ref "L1") (pin "2") (pinfunction "2_2") (pintype "passive"))
      (node (ref "U$6") (pin "1") (pinfunction "1_1") (pintype "bidirectional"))
    )
    (net (code "30") (name "/VCC") (class "Default")
      (node (ref "C10") (pin "2") (pinfunction "2_2") (pintype "passive"))
      (node (ref "C14") (pin "2") (pinfunction "2_2") (pintype "passive"))
      (node (ref "C15") (pin "2") (pinfunction "2_2") (pintype "passive"))
      (node (ref "C4") (pin "1") (pinfunction "1_1") (pintype "passive"))
      (node (ref "C5") (pin "2") (pinfunction "2_2") (pintype "passive"))
      (node (ref "ICSP") (pin "6") (pinfunction "VCC_6") (pintype "bidirectional"))
      (node (ref "L1") (pin "1") (pinfunction "1_1") (pintype "passive"))
      (node (ref "L2") (pin "2") (pinfunction "2_2") (pintype "passive"))
      (node (ref "R3") (pin "1") (pinfunction "1_1") (pintype "passive"))
      (node (ref "R5") (pin "1") (pinfunction "1_1") (pintype "passive"))
      (node (ref "R6") (pin "2") (pinfunction "2_2") (pintype "passive"))
      (node (ref "U1") (pin "14") (pinfunction "VCC_14") (pintype "bidirectional"))
      (node (ref "U1") (pin "2") (pinfunction "UVCC_2") (pintype "bidirectional"))
      (node (ref "U1") (pin "34") (pinfunction "VCC_34") (pintype "bidirectional"))
      (node (ref "U1") (pin "7") (pinfunction "VBUS_7") (pintype "bidirectional"))
    )
    (net (code "31") (name "/X1") (class "Default")
      (node (ref "R7") (pin "2") (pinfunction "2_2") (pintype "passive"))
      (node (ref "U$1") (pin "P$1") (pinfunction "P$1_P$1") (pintype "bidirectional"))
      (node (ref "U$18") (pin "P$1") (pinfunction "P$1_P$1") (pintype "bidirectional"))
      (node (ref "U$2") (pin "P$1") (pinfunction "P$1_P$1") (pintype "bidirectional"))
      (node (ref "U$26") (pin "P$1") (pinfunction "P$1_P$1") (pintype "bidirectional"))
      (node (ref "U$34") (pin "P$1") (pinfunction "P$1_P$1") (pintype "bidirectional"))
      (node (ref "U$42") (pin "P$1") (pinfunction "P$1_P$1") (pintype "bidirectional"))
      (node (ref "U$50") (pin "P$1") (pinfunction "P$1_P$1") (pintype "bidirectional"))
    )
    (net (code "32") (name "/X1_UC") (class "Default")
      (node (ref "R7") (pin "1") (pinfunction "1_1") (pintype "passive"))
      (node (ref "U1") (pin "41") (pinfunction "PF0(ADC0)_41") (pintype "bidirectional"))
    )
    (net (code "33") (name "/X2") (class "Default")
      (node (ref "R10") (pin "2") (pinfunction "2_2") (pintype "passive"))
      (node (ref "U$11") (pin "P$1") (pinfunction "P$1_P$1") (pintype "bidirectional"))
      (node (ref "U$19") (pin "P$1") (pinfunction "P$1_P$1") (pintype "bidirectional"))
      (node (ref "U$27") (pin "P$1") (pinfunction "P$1_P$1") (pintype "bidirectional"))
      (node (ref "U$3") (pin "P$1") (pinfunction "P$1_P$1") (pintype "bidirectional"))
      (node (ref "U$35") (pin "P$1") (pinfunction "P$1_P$1") (pintype "bidirectional"))
      (node (ref "U$43") (pin "P$1") (pinfunction "P$1_P$1") (pintype "bidirectional"))
      (node (ref "U$51") (pin "P$1") (pinfunction "P$1_P$1") (pintype "bidirectional"))
    )
    (net (code "34") (name "/X2_UC") (class "Default")
      (node (ref "R10") (pin "1") (pinfunction "1_1") (pintype "passive"))
      (node (ref "U1") (pin "39") (pinfunction "PF4(ADC4)_39") (pintype "bidirectional"))
    )
    (net (code "35") (name "/X3") (class "Default")
      (node (ref "R11") (pin "2") (pinfunction "2_2") (pintype "passive"))
      (node (ref "U$12") (pin "P$1") (pinfunction "P$1_P$1") (pintype "bidirectional"))
      (node (ref "U$20") (pin "P$1") (pinfunction "P$1_P$1") (pintype "bidirectional"))
      (node (ref "U$28") (pin "P$1") (pinfunction "P$1_P$1") (pintype "bidirectional"))
      (node (ref "U$36") (pin "P$1") (pinfunction "P$1_P$1") (pintype "bidirectional"))
      (node (ref "U$4") (pin "P$1") (pinfunction "P$1_P$1") (pintype "bidirectional"))
      (node (ref "U$44") (pin "P$1") (pinfunction "P$1_P$1") (pintype "bidirectional"))
      (node (ref "U$52") (pin "P$1") (pinfunction "P$1_P$1") (pintype "bidirectional"))
    )
    (net (code "36") (name "/X3_UC") (class "Default")
      (node (ref "R11") (pin "1") (pinfunction "1_1") (pintype "passive"))
      (node (ref "U1") (pin "38") (pinfunction "PF5(ADC5)_38") (pintype "bidirectional"))
    )
    (net (code "37") (name "/X4") (class "Default")
      (node (ref "R12") (pin "2") (pinfunction "2_2") (pintype "passive"))
      (node (ref "U$13") (pin "P$1") (pinfunction "P$1_P$1") (pintype "bidirectional"))
      (node (ref "U$21") (pin "P$1") (pinfunction "P$1_P$1") (pintype "bidirectional"))
      (node (ref "U$29") (pin "P$1") (pinfunction "P$1_P$1") (pintype "bidirectional"))
      (node (ref "U$37") (pin "P$1") (pinfunction "P$1_P$1") (pintype "bidirectional"))
      (node (ref "U$45") (pin "P$1") (pinfunction "P$1_P$1") (pintype "bidirectional"))
      (node (ref "U$5") (pin "P$1") (pinfunction "P$1_P$1") (pintype "bidirectional"))
      (node (ref "U$53") (pin "P$1") (pinfunction "P$1_P$1") (pintype "bidirectional"))
    )
    (net (code "38") (name "/X4_UC") (class "Default")
      (node (ref "R12") (pin "1") (pinfunction "1_1") (pintype "passive"))
      (node (ref "U1") (pin "37") (pinfunction "PF6(ADC6)_37") (pintype "bidirectional"))
    )
    (net (code "39") (name "/X5") (class "Default")
      (node (ref "R13") (pin "2") (pinfunction "2_2") (pintype "passive"))
      (node (ref "U$14") (pin "P$1") (pinfunction "P$1_P$1") (pintype "bidirectional"))
      (node (ref "U$22") (pin "P$1") (pinfunction "P$1_P$1") (pintype "bidirectional"))
      (node (ref "U$30") (pin "P$1") (pinfunction "P$1_P$1") (pintype "bidirectional"))
      (node (ref "U$38") (pin "P$1") (pinfunction "P$1_P$1") (pintype "bidirectional"))
      (node (ref "U$46") (pin "P$1") (pinfunction "P$1_P$1") (pintype "bidirectional"))
      (node (ref "U$54") (pin "P$1") (pinfunction "P$1_P$1") (pintype "bidirectional"))
      (node (ref "U$7") (pin "P$1") (pinfunction "P$1_P$1") (pintype "bidirectional"))
    )
    (net (code "40") (name "/X5_UC") (class "Default")
      (node (ref "R13") (pin "1") (pinfunction "1_1") (pintype "passive"))
      (node (ref "U1") (pin "36") (pinfunction "PF7(ADC7)_36") (pintype "bidirectional"))
    )
    (net (code "41") (name "/X6") (class "Default")
      (node (ref "R14") (pin "2") (pinfunction "2_2") (pintype "passive"))
      (node (ref "U$15") (pin "P$1") (pinfunction "P$1_P$1") (pintype "bidirectional"))
      (node (ref "U$23") (pin "P$1") (pinfunction "P$1_P$1") (pintype "bidirectional"))
      (node (ref "U$31") (pin "P$1") (pinfunction "P$1_P$1") (pintype "bidirectional"))
      (node (ref "U$39") (pin "P$1") (pinfunction "P$1_P$1") (pintype "bidirectional"))
      (node (ref "U$47") (pin "P$1") (pinfunction "P$1_P$1") (pintype "bidirectional"))
      (node (ref "U$55") (pin "P$1") (pinfunction "P$1_P$1") (pintype "bidirectional"))
      (node (ref "U$8") (pin "P$1") (pinfunction "P$1_P$1") (pintype "bidirectional"))
    )
    (net (code "42") (name "/X6_UC") (class "Default")
      (node (ref "R14") (pin "1") (pinfunction "1_1") (pintype "passive"))
      (node (ref "U1") (pin "25") (pinfunction "PD4(ADC8)_25") (pintype "bidirectional"))
    )
    (net (code "43") (name "/X7") (class "Default")
      (node (ref "R15") (pin "2") (pinfunction "2_2") (pintype "passive"))
      (node (ref "U$16") (pin "P$1") (pinfunction "P$1_P$1") (pintype "bidirectional"))
      (node (ref "U$24") (pin "P$1") (pinfunction "P$1_P$1") (pintype "bidirectional"))
      (node (ref "U$32") (pin "P$1") (pinfunction "P$1_P$1") (pintype "bidirectional"))
      (node (ref "U$40") (pin "P$1") (pinfunction "P$1_P$1") (pintype "bidirectional"))
      (node (ref "U$48") (pin "P$1") (pinfunction "P$1_P$1") (pintype "bidirectional"))
      (node (ref "U$56") (pin "P$1") (pinfunction "P$1_P$1") (pintype "bidirectional"))
      (node (ref "U$9") (pin "P$1") (pinfunction "P$1_P$1") (pintype "bidirectional"))
    )
    (net (code "44") (name "/X7_UC") (class "Default")
      (node (ref "R15") (pin "1") (pinfunction "1_1") (pintype "passive"))
      (node (ref "U1") (pin "26") (pinfunction "PD6(ADC9)_26") (pintype "bidirectional"))
    )
    (net (code "45") (name "/X8") (class "Default")
      (node (ref "R16") (pin "2") (pinfunction "2_2") (pintype "passive"))
      (node (ref "U$10") (pin "P$1") (pinfunction "P$1_P$1") (pintype "bidirectional"))
      (node (ref "U$17") (pin "P$1") (pinfunction "P$1_P$1") (pintype "bidirectional"))
      (node (ref "U$25") (pin "P$1") (pinfunction "P$1_P$1") (pintype "bidirectional"))
      (node (ref "U$33") (pin "P$1") (pinfunction "P$1_P$1") (pintype "bidirectional"))
      (node (ref "U$41") (pin "P$1") (pinfunction "P$1_P$1") (pintype "bidirectional"))
      (node (ref "U$49") (pin "P$1") (pinfunction "P$1_P$1") (pintype "bidirectional"))
      (node (ref "U$57") (pin "P$1") (pinfunction "P$1_P$1") (pintype "bidirectional"))
    )
    (net (code "46") (name "/X8_UC") (class "Default")
      (node (ref "R16") (pin "1") (pinfunction "1_1") (pintype "passive"))
      (node (ref "U1") (pin "27") (pinfunction "PD7(ADC10)_27") (pintype "bidirectional"))
    )
    (net (code "47") (name "/Y1") (class "Default")
      (node (ref "R17") (pin "2") (pinfunction "2_2") (pintype "passive"))
      (node (ref "U$105") (pin "P$1") (pinfunction "P$1_P$1") (pintype "bidirectional"))
      (node (ref "U$111") (pin "P$1") (pinfunction "P$1_P$1") (pintype "bidirectional"))
      (node (ref "U$63") (pin "P$1") (pinfunction "P$1_P$1") (pintype "bidirectional"))
      (node (ref "U$69") (pin "P$1") (pinfunction "P$1_P$1") (pintype "bidirectional"))
      (node (ref "U$75") (pin "P$1") (pinfunction "P$1_P$1") (pintype "bidirectional"))
      (node (ref "U$81") (pin "P$1") (pinfunction "P$1_P$1") (pintype "bidirectional"))
      (node (ref "U$87") (pin "P$1") (pinfunction "P$1_P$1") (pintype "bidirectional"))
      (node (ref "U$93") (pin "P$1") (pinfunction "P$1_P$1") (pintype "bidirectional"))
      (node (ref "U$99") (pin "P$1") (pinfunction "P$1_P$1") (pintype "bidirectional"))
    )
    (net (code "48") (name "/Y1_UC") (class "Default")
      (node (ref "R17") (pin "1") (pinfunction "1_1") (pintype "passive"))
      (node (ref "U1") (pin "28") (pinfunction "PB4(ADC11)_28") (pintype "bidirectional"))
    )
    (net (code "49") (name "/Y2") (class "Default")
      (node (ref "R18") (pin "2") (pinfunction "2_2") (pintype "passive"))
      (node (ref "U$104") (pin "P$1") (pinfunction "P$1_P$1") (pintype "bidirectional"))
      (node (ref "U$110") (pin "P$1") (pinfunction "P$1_P$1") (pintype "bidirectional"))
      (node (ref "U$62") (pin "P$1") (pinfunction "P$1_P$1") (pintype "bidirectional"))
      (node (ref "U$68") (pin "P$1") (pinfunction "P$1_P$1") (pintype "bidirectional"))
      (node (ref "U$74") (pin "P$1") (pinfunction "P$1_P$1") (pintype "bidirectional"))
      (node (ref "U$80") (pin "P$1") (pinfunction "P$1_P$1") (pintype "bidirectional"))
      (node (ref "U$86") (pin "P$1") (pinfunction "P$1_P$1") (pintype "bidirectional"))
      (node (ref "U$92") (pin "P$1") (pinfunction "P$1_P$1") (pintype "bidirectional"))
      (node (ref "U$98") (pin "P$1") (pinfunction "P$1_P$1") (pintype "bidirectional"))
    )
    (net (code "50") (name "/Y2_UC") (class "Default")
      (node (ref "R18") (pin "1") (pinfunction "1_1") (pintype "passive"))
      (node (ref "U1") (pin "29") (pinfunction "PB5(ADC12)_29") (pintype "bidirectional"))
    )
    (net (code "51") (name "/Y3") (class "Default")
      (node (ref "R19") (pin "2") (pinfunction "2_2") (pintype "passive"))
      (node (ref "U$103") (pin "P$1") (pinfunction "P$1_P$1") (pintype "bidirectional"))
      (node (ref "U$109") (pin "P$1") (pinfunction "P$1_P$1") (pintype "bidirectional"))
      (node (ref "U$61") (pin "P$1") (pinfunction "P$1_P$1") (pintype "bidirectional"))
      (node (ref "U$67") (pin "P$1") (pinfunction "P$1_P$1") (pintype "bidirectional"))
      (node (ref "U$73") (pin "P$1") (pinfunction "P$1_P$1") (pintype "bidirectional"))
      (node (ref "U$79") (pin "P$1") (pinfunction "P$1_P$1") (pintype "bidirectional"))
      (node (ref "U$85") (pin "P$1") (pinfunction "P$1_P$1") (pintype "bidirectional"))
      (node (ref "U$91") (pin "P$1") (pinfunction "P$1_P$1") (pintype "bidirectional"))
      (node (ref "U$97") (pin "P$1") (pinfunction "P$1_P$1") (pintype "bidirectional"))
    )
    (net (code "52") (name "/Y3_UC") (class "Default")
      (node (ref "R19") (pin "1") (pinfunction "1_1") (pintype "passive"))
    )
    (net (code "53") (name "/Y4") (class "Default")
      (node (ref "U$102") (pin "P$1") (pinfunction "P$1_P$1") (pintype "bidirectional"))
      (node (ref "U$108") (pin "P$1") (pinfunction "P$1_P$1") (pintype "bidirectional"))
      (node (ref "U$60") (pin "P$1") (pinfunction "P$1_P$1") (pintype "bidirectional"))
      (node (ref "U$66") (pin "P$1") (pinfunction "P$1_P$1") (pintype "bidirectional"))
      (node (ref "U$72") (pin "P$1") (pinfunction "P$1_P$1") (pintype "bidirectional"))
      (node (ref "U$78") (pin "P$1") (pinfunction "P$1_P$1") (pintype "bidirectional"))
      (node (ref "U$84") (pin "P$1") (pinfunction "P$1_P$1") (pintype "bidirectional"))
      (node (ref "U$90") (pin "P$1") (pinfunction "P$1_P$1") (pintype "bidirectional"))
      (node (ref "U$96") (pin "P$1") (pinfunction "P$1_P$1") (pintype "bidirectional"))
    )
    (net (code "54") (name "/Y5") (class "Default")
      (node (ref "U$101") (pin "P$1") (pinfunction "P$1_P$1") (pintype "bidirectional"))
      (node (ref "U$107") (pin "P$1") (pinfunction "P$1_P$1") (pintype "bidirectional"))
      (node (ref "U$59") (pin "P$1") (pinfunction "P$1_P$1") (pintype "bidirectional"))
      (node (ref "U$65") (pin "P$1") (pinfunction "P$1_P$1") (pintype "bidirectional"))
      (node (ref "U$71") (pin "P$1") (pinfunction "P$1_P$1") (pintype "bidirectional"))
      (node (ref "U$77") (pin "P$1") (pinfunction "P$1_P$1") (pintype "bidirectional"))
      (node (ref "U$83") (pin "P$1") (pinfunction "P$1_P$1") (pintype "bidirectional"))
      (node (ref "U$89") (pin "P$1") (pinfunction "P$1_P$1") (pintype "bidirectional"))
      (node (ref "U$95") (pin "P$1") (pinfunction "P$1_P$1") (pintype "bidirectional"))
    )
    (net (code "55") (name "/Y6") (class "Default")
      (node (ref "U$100") (pin "P$1") (pinfunction "P$1_P$1") (pintype "bidirectional"))
      (node (ref "U$106") (pin "P$1") (pinfunction "P$1_P$1") (pintype "bidirectional"))
      (node (ref "U$58") (pin "P$1") (pinfunction "P$1_P$1") (pintype "bidirectional"))
      (node (ref "U$64") (pin "P$1") (pinfunction "P$1_P$1") (pintype "bidirectional"))
      (node (ref "U$70") (pin "P$1") (pinfunction "P$1_P$1") (pintype "bidirectional"))
      (node (ref "U$76") (pin "P$1") (pinfunction "P$1_P$1") (pintype "bidirectional"))
      (node (ref "U$82") (pin "P$1") (pinfunction "P$1_P$1") (pintype "bidirectional"))
      (node (ref "U$88") (pin "P$1") (pinfunction "P$1_P$1") (pintype "bidirectional"))
      (node (ref "U$94") (pin "P$1") (pinfunction "P$1_P$1") (pintype "bidirectional"))
    )
    (net (code "56") (name "GND") (class "Default")
      (node (ref "C1") (pin "1") (pinfunction "1_1") (pintype "passive"))
      (node (ref "C10") (pin "1") (pinfunction "1_1") (pintype "passive"))
      (node (ref "C13") (pin "1") (pinfunction "1_1") (pintype "passive"))
      (node (ref "C14") (pin "1") (pinfunction "1_1") (pintype "passive"))
      (node (ref "C15") (pin "1") (pinfunction "1_1") (pintype "passive"))
      (node (ref "C2") (pin "1") (pinfunction "1_1") (pintype "passive"))
      (node (ref "C3") (pin "1") (pinfunction "1_1") (pintype "passive"))
      (node (ref "C4") (pin "2") (pinfunction "2_2") (pintype "passive"))
      (node (ref "C5") (pin "1") (pinfunction "1_1") (pintype "passive"))
      (node (ref "ICSP") (pin "5") (pinfunction "GND_5") (pintype "bidirectional"))
      (node (ref "SH1") (pin "2") (pinfunction "P$2_2") (pintype "bidirectional"))
      (node (ref "U$6") (pin "5") (pinfunction "5_5") (pintype "bidirectional"))
      (node (ref "U1") (pin "15") (pinfunction "GND_15") (pintype "bidirectional"))
      (node (ref "U1") (pin "35") (pinfunction "GND_35") (pintype "bidirectional"))
      (node (ref "U1") (pin "5") (pinfunction "UGND_5") (pintype "bidirectional"))
    )
    (net (code "57") (name "Net-(D2-PadA)") (class "Default")
      (node (ref "D2") (pin "A") (pinfunction "A_A") (pintype "bidirectional"))
      (node (ref "R5") (pin "2") (pinfunction "2_2") (pintype "passive"))
    )
    (net (code "58") (name "Net-(D3-PadA)") (class "Default")
      (node (ref "D3") (pin "A") (pinfunction "A_A") (pintype "bidirectional"))
      (node (ref "R3") (pin "2") (pinfunction "2_2") (pintype "passive"))
    )
    (net (code "59") (name "Net-(U1-XTAL1)") (class "Default")
      (node (ref "C2") (pin "2") (pinfunction "2_2") (pintype "passive"))
      (node (ref "U1") (pin "17") (pinfunction "XTAL1_17") (pintype "bidirectional"))
      (node (ref "X1") (pin "3") (pinfunction "2_3") (pintype "passive"))
    )
    (net (code "60") (name "Net-(U1-XTAL2)") (class "Default")
      (node (ref "C3") (pin "2") (pinfunction "2_2") (pintype "passive"))
      (node (ref "U1") (pin "16") (pinfunction "XTAL2_16") (pintype "bidirectional"))
      (node (ref "X1") (pin "1") (pinfunction "1_1") (pintype "passive"))
    )
    (net (code "61") (name "unconnected-(U$6-Pad4)") (class "Default")
      (node (ref "U$6") (pin "4") (pinfunction "4_4") (pintype "bidirectional"))
    )
  )
)
